# Other.net
KiCad netlist of a schematic drawn in Altium Designer
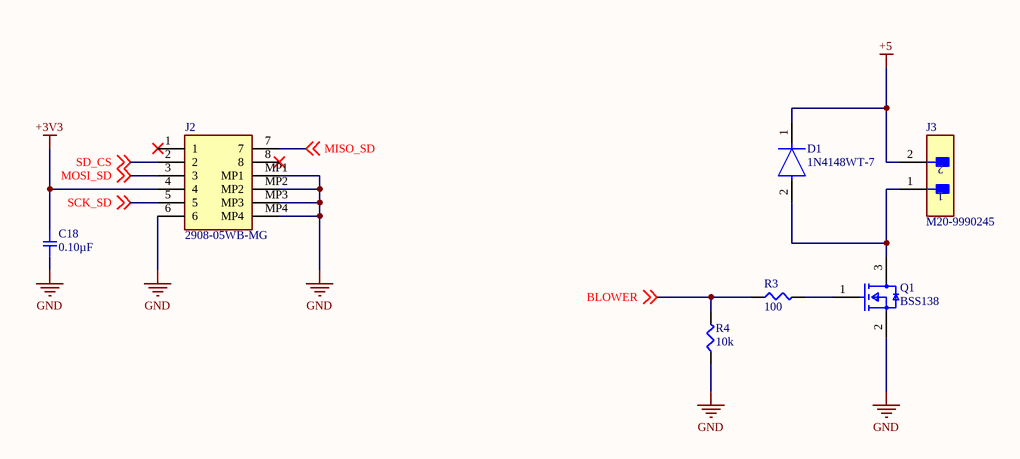
[diagram p0: Other.SchDoc]

(export (version "E")
  (design (tool "Eeschema 10.0.6"))
  (components
    (comp (ref "C18")
      (value "0.10µF")
      (footprint "SMD-0402C")
      (description "CAP CER 0.1UF 16V X7R 0402")
      (fields
        (field (name "DIGI-KEY PART NUMBER") "490-4759-1-ND")
        (field (name "PART NUMBER") "GCM155R71C104KA55D")
      )
      (libsource (lib "capacitor_murata_0402") (part "GCM155R71C104KA55D"))
    )
    (comp (ref "D1")
      (value "1N4148WT-7")
      (footprint "FP-SOD523-MFG")
      (description "DIODE GEN PURP 80V 125MA SOD523")
      (libsource (lib "Altium Content Vault") (part "d7152d700b627762746794eb795d46e"))
    )
    (comp (ref "J2")
      (value "2908-05WB-MG")
      (footprint "SamacSys:290805WBMG")
      (description "Connector")
      (fields (field (name "MOUSER PART NUMBER") "517-2908-05WB-MG"))
      (libsource (lib "*") (part "2908-05WB-MG"))
    )
    (comp (ref "J3")
      (value "M20-9990245")
      (footprint "FP-M20-9990245-MFG")
      (description "CONN HEADER VERT 2POS 2.54MM")
      (fields (field (name "VOLTAGE") "50V"))
      (libsource (lib "Altium Content Vault") (part "3bc925449376181038e59eaffc5286c"))
    )
    (comp (ref "Q1")
      (value "BSS138")
      (footprint "FP-318-08-IPC_A")
      (description "MOSFET N-CH 50V 220MA SOT-23")
      (libsource (lib "Altium Content Vault") (part "3b9c635fedb024a5347a57b145af9cc"))
    )
    (comp (ref "R3")
      (value "100")
      (footprint "SMD-0402-RES")
      (description "RES SMD 100 OHM 1% 1/10W 0402")
      (fields (field (name "PART NUMBER") "ERJ-2RKF1000X") (field (name "DIGI-KEY PART NUMBER") "P100LCT-ND"))
      (libsource (lib "Panasonic_ERJ_0402") (part "ERJ-2RKF1000X"))
    )
    (comp (ref "R4")
      (value "10k")
      (footprint "SMD-0402-RES")
      (description "RES SMD 10K OHM 5% 1/10W 0402")
      (fields (field (name "PART NUMBER") "ERJ-2GEJ103X") (field (name "DIGI-KEY PART NUMBER") "P10KJCT-ND"))
      (libsource (lib "Panasonic_ERJ_0402") (part "ERJ-2GEJ103X"))
    )
  )
  (nets
    (net (code "1") (name "+3V3") (class "Default")
      (node (ref "C18") (pin "1") (pinfunction "1_1") (pintype "passive"))
      (node (ref "J2") (pin "4") (pinfunction "4_4") (pintype "passive"))
    )
    (net (code "2") (name "+5") (class "Default")
      (node (ref "D1") (pin "1") (pinfunction "C_1") (pintype "passive"))
      (node (ref "J3") (pin "2") (pinfunction "2_2") (pintype "passive"))
    )
    (net (code "3") (name "BLOWER") (class "Default")
      (node (ref "R3") (pin "1") (pinfunction "1_1") (pintype "passive"))
      (node (ref "R4") (pin "2") (pinfunction "2_2") (pintype "passive"))
    )
    (net (code "4") (name "GND") (class "Default")
      (node (ref "C18") (pin "2") (pinfunction "2_2") (pintype "passive"))
      (node (ref "J2") (pin "6") (pinfunction "6_6") (pintype "passive"))
      (node (ref "J2") (pin "MP1") (pinfunction "MP1_MP1") (pintype "passive"))
      (node (ref "J2") (pin "MP2") (pinfunction "MP2_MP2") (pintype "passive"))
      (node (ref "J2") (pin "MP3") (pinfunction "MP3_MP3") (pintype "passive"))
      (node (ref "J2") (pin "MP4") (pinfunction "MP4_MP4") (pintype "passive"))
      (node (ref "Q1") (pin "2") (pinfunction "S_2") (pintype "passive"))
      (node (ref "R4") (pin "1") (pinfunction "1_1") (pintype "passive"))
    )
    (net (code "5") (name "MISO_SD") (class "Default")
      (node (ref "J2") (pin "7") (pinfunction "7_7") (pintype "passive"))
    )
    (net (code "6") (name "MOSI_SD") (class "Default")
      (node (ref "J2") (pin "3") (pinfunction "3_3") (pintype "passive"))
    )
    (net (code "7") (name "Net-(D1-A)") (class "Default")
      (node (ref "D1") (pin "2") (pinfunction "A_2") (pintype "passive"))
      (node (ref "J3") (pin "1") (pinfunction "1_1") (pintype "passive"))
      (node (ref "Q1") (pin "3") (pinfunction "D_3") (pintype "passive"))
    )
    (net (code "8") (name "Net-(Q1-G)") (class "Default")
      (node (ref "Q1") (pin "1") (pinfunction "G_1") (pintype "passive"))
      (node (ref "R3") (pin "2") (pinfunction "2_2") (pintype "passive"))
    )
    (net (code "9") (name "SCK_SD") (class "Default")
      (node (ref "J2") (pin "5") (pinfunction "5_5") (pintype "passive"))
    )
    (net (code "10") (name "SD_CS") (class "Default")
      (node (ref "J2") (pin "2") (pinfunction "2_2") (pintype "passive"))
    )
    (net (code "11") (name "unconnected-(J2-Pad1)") (class "Default")
      (node (ref "J2") (pin "1") (pinfunction "1_1") (pintype "passive+no_connect"))
    )
    (net (code "12") (name "unconnected-(J2-Pad8)") (class "Default")
      (node (ref "J2") (pin "8") (pinfunction "8_8") (pintype "passive+no_connect"))
    )
  )
)
